# PWR_3V3.net
KiCad netlist of a schematic drawn in Altium Designer
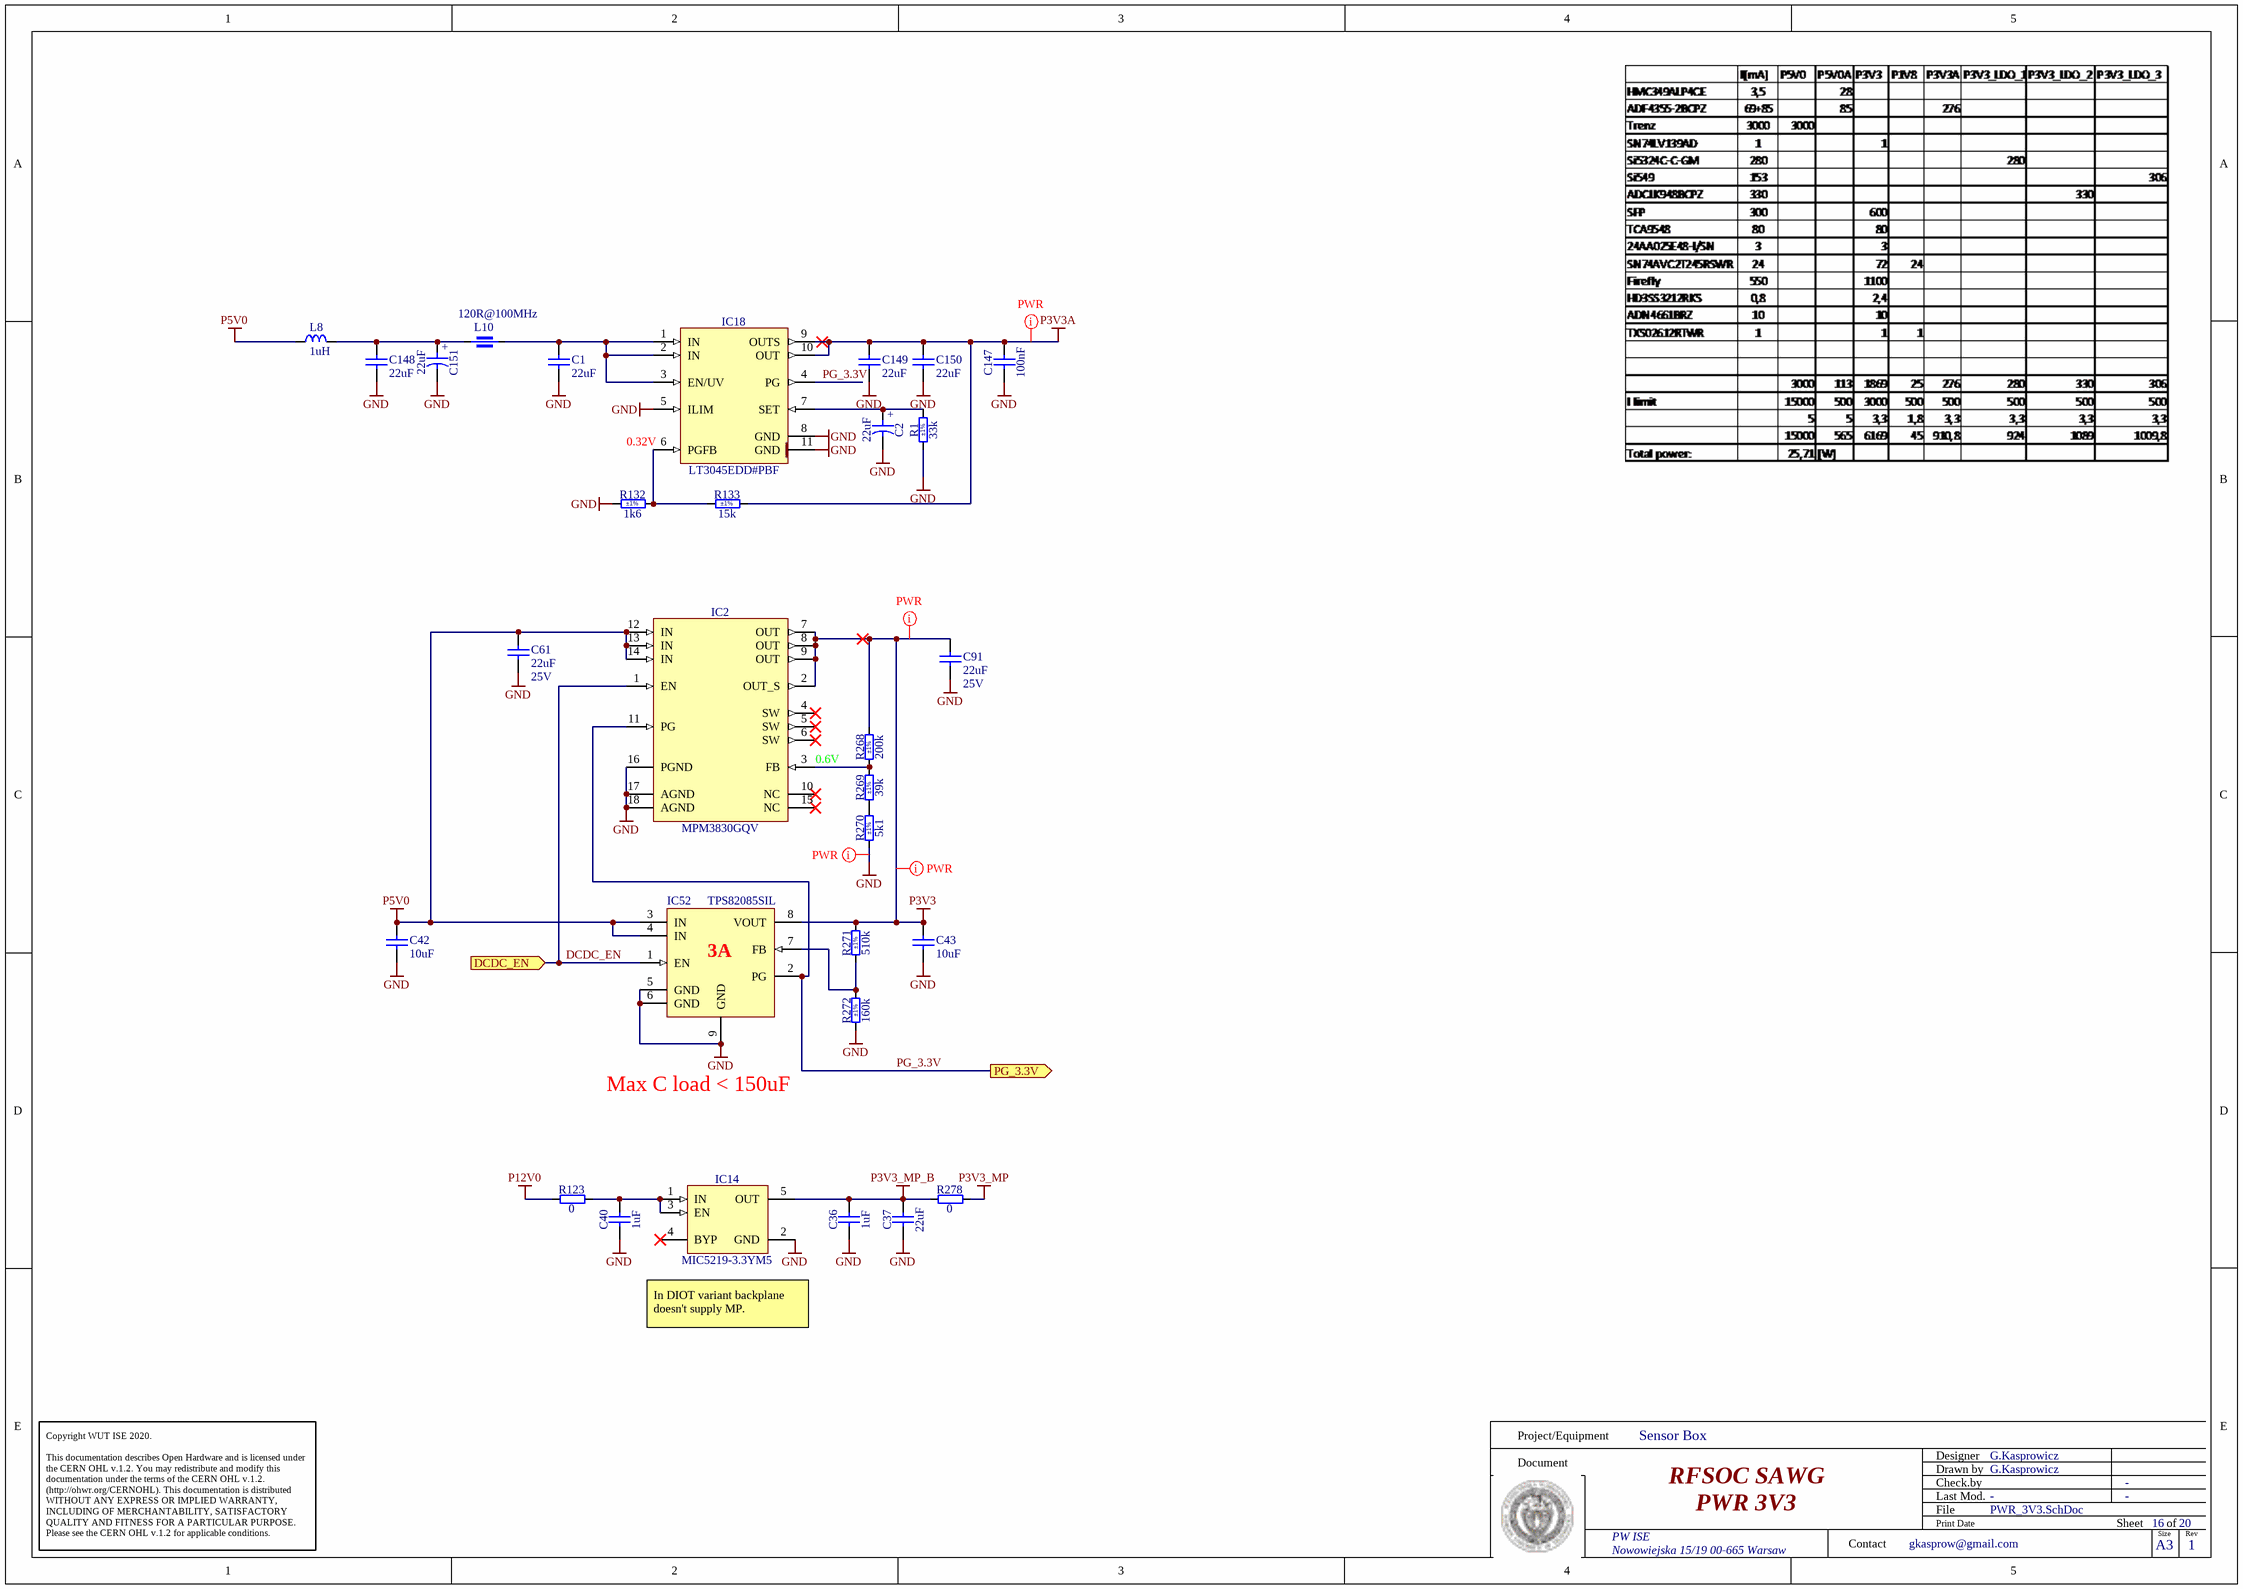
[diagram p0: PWR_3V3.SchDoc]

(export (version "E")
  (design (tool "Eeschema 10.0.6"))
  (components
    (comp (ref "C1")
      (value "22uF")
      (footprint "CAPC2012X135N")
      (description "Non-polarised capacitor")
      (fields
        (field (name "PART NUMBER") "CC0805_22UF_16V_10%_X5R")
        (field (name "VOLTAGE") "16V")
        (field (name "AUTHOR") "CERN DEM JLC")
      )
      (libsource (lib "Capacitors") (part "Capacitor - non polarized"))
    )
    (comp (ref "C2")
      (value "22uF")
      (footprint "CAPMP3528X210N")
      (description "Polarised capacitor")
      (fields
        (field (name "PART NUMBER") "CTE3528-21_22UF_10V_10%_LESR0700")
        (field (name "VOLTAGE") "10V")
        (field (name "AUTHOR") "CERN DEM JLC")
      )
      (libsource (lib "Capacitors") (part "Capacitor - polarized"))
    )
    (comp (ref "C36")
      (value "1uF")
      (footprint "CAPC1608X87N")
      (description "Non-polarised capacitor")
      (fields
        (field (name "PART NUMBER") "CC0603_1UF_25V_10%_X7R")
        (field (name "VOLTAGE") "25V")
        (field (name "AUTHOR") "CERN DEM JLC")
      )
      (libsource (lib "Capacitors") (part "Capacitor - non polarized"))
    )
    (comp (ref "C37")
      (value "22uF")
      (footprint "CAPC1608X90N")
      (description "Non-polarised capacitor")
      (fields
        (field (name "PART NUMBER") "CC0603_22UF_6.3V_20%_X5R")
        (field (name "VOLTAGE") "6.3V")
        (field (name "AUTHOR") "CERN DEM JLC")
      )
      (libsource (lib "Capacitors") (part "Capacitor - non polarized"))
    )
    (comp (ref "C40")
      (value "1uF")
      (footprint "CAPC1608X87N")
      (description "Non-polarised capacitor")
      (fields
        (field (name "PART NUMBER") "CC0603_1UF_25V_10%_X7R")
        (field (name "VOLTAGE") "25V")
        (field (name "AUTHOR") "CERN DEM JLC")
      )
      (libsource (lib "Capacitors") (part "Capacitor - non polarized"))
    )
    (comp (ref "C42")
      (value "10uF")
      (footprint "CAPC1608X80N")
      (description "Non-polarised capacitor")
      (fields
        (field (name "VOLTAGE") "16V")
        (field (name "TOLERANCE") "±20%")
        (field (name "AUTHOR") "CERN DEM MR")
      )
      (libsource (lib "Capacitors") (part "Capacitor - non polarized"))
    )
    (comp (ref "C43")
      (value "10uF")
      (footprint "CAPC1608X80N")
      (description "Non-polarised capacitor")
      (fields
        (field (name "VOLTAGE") "16V")
        (field (name "TOLERANCE") "±20%")
        (field (name "AUTHOR") "CERN DEM MR")
      )
      (libsource (lib "Capacitors") (part "Capacitor - non polarized"))
    )
    (comp (ref "C61")
      (value "22uF")
      (footprint "CAPC2012X145N")
      (description "Non-polarised capacitor")
      (fields
        (field (name "VOLTAGE") "25V")
        (field (name "TOLERANCE") "±20%")
        (field (name "PART NUMBER") "CC0805_22UF_25V_20%_X5R")
        (field (name "AUTHOR") "CERN DEM WB")
      )
      (libsource (lib "Capacitors") (part "Capacitor - non polarized"))
    )
    (comp (ref "C91")
      (value "22uF")
      (footprint "CAPC2012X145N")
      (description "Non-polarised capacitor")
      (fields
        (field (name "VOLTAGE") "25V")
        (field (name "TOLERANCE") "±20%")
        (field (name "PART NUMBER") "CC0805_22UF_25V_20%_X5R")
        (field (name "AUTHOR") "CERN DEM WB")
      )
      (libsource (lib "Capacitors") (part "Capacitor - non polarized"))
    )
    (comp (ref "C147")
      (value "100nF")
      (footprint "CAPC1005X55N")
      (description "Non-polarised capacitor")
      (fields
        (field (name "PART NUMBER") "CC0402_100NF_16V_10%_X5R")
        (field (name "VOLTAGE") "16V")
        (field (name "AUTHOR") "CERN DEM JLC")
      )
      (libsource (lib "Capacitors") (part "Capacitor - non polarized"))
    )
    (comp (ref "C148")
      (value "22uF")
      (footprint "CAPC2012X135N")
      (description "Non-polarised capacitor")
      (fields
        (field (name "PART NUMBER") "CC0805_22UF_16V_10%_X5R")
        (field (name "VOLTAGE") "16V")
        (field (name "AUTHOR") "CERN DEM JLC")
      )
      (libsource (lib "Capacitors") (part "Capacitor - non polarized"))
    )
    (comp (ref "C149")
      (value "22uF")
      (footprint "CAPC2012X135N")
      (description "Non-polarised capacitor")
      (fields
        (field (name "PART NUMBER") "CC0805_22UF_16V_10%_X5R")
        (field (name "VOLTAGE") "16V")
        (field (name "AUTHOR") "CERN DEM JLC")
      )
      (libsource (lib "Capacitors") (part "Capacitor - non polarized"))
    )
    (comp (ref "C150")
      (value "22uF")
      (footprint "CAPC2012X135N")
      (description "Non-polarised capacitor")
      (fields
        (field (name "PART NUMBER") "CC0805_22UF_16V_10%_X5R")
        (field (name "VOLTAGE") "16V")
        (field (name "AUTHOR") "CERN DEM JLC")
      )
      (libsource (lib "Capacitors") (part "Capacitor - non polarized"))
    )
    (comp (ref "C151")
      (value "22uF")
      (footprint "CAPMP3528X210N")
      (description "Polarised capacitor")
      (fields
        (field (name "PART NUMBER") "CTE3528-21_22UF_10V_10%_LESR0700")
        (field (name "VOLTAGE") "10V")
        (field (name "AUTHOR") "CERN DEM JLC")
      )
      (libsource (lib "Capacitors") (part "Capacitor - polarized"))
    )
    (comp (ref "IC2")
      (value "MPM3830GQV")
      (footprint "MPS_MPM38XXGQV")
      (description "2.8V to 5.5V Input, 4A, Power Module Synchronous Step-Down Converter with Integrated Inductor")
      (fields
        (field (name "MANUFACTURER") "MPS (MONOLITIC  POWER SYSTEMS)")
        (field (name "AUTHOR") "CERN DEM BC")
      )
      (libsource (lib "ICs And Semiconductors") (part "MPM3830GQV"))
    )
    (comp (ref "IC14")
      (value "MIC5219-3.3YM5")
      (footprint "SOT95P280X145-5N")
      (description "500mA Peak Output LDO Regulator")
      (fields (field (name "MANUFACTURER") "MICROCHIP TECHNOLOGY") (field (name "AUTHOR") "CERN DEM WB"))
      (libsource (lib "ICs And Semiconductors") (part "MIC5219-X.XYM5"))
    )
    (comp (ref "IC18")
      (value "LT3045EDD#PBF")
      (footprint "SON50P300X300X80-11N-R175X248")
      (description "20V, 500mA, Ultralow Noise, Ultrahigh PSRR Linear Regulator")
      (fields (field (name "MANUFACTURER") "LINEAR TECHNOLOGY") (field (name "AUTHOR") "CERN DEM JLC"))
      (libsource (lib "ICs And Semiconductors") (part "LT3045EDD"))
    )
    (comp (ref "IC52")
      (value "TPS82085SIL")
      (footprint "TPS82085SILR")
      (libsource (lib "TE") (part "TPS82085"))
    )
    (comp (ref "L8")
      (value "1uH")
      (footprint "INDC2520X120N")
      (description "Inductor")
      (fields
        (field (name "TOLERANCE") "±20%")
        (field (name "PART NUMBER") "IND1008_1UH_20%_TDK_TFM252012ALVA1R0M")
        (field (name "AUTHOR") "CERN DEM BC")
      )
      (libsource (lib "Inductors & Transformers") (part "Inductor"))
    )
    (comp (ref "L10")
      (value "120R@100MHz")
      (footprint "INDC1608X65N")
      (fields
        (field (name "PART NUMBER") "IND0603_MURATA_BLM18SG121TN1D")
        (field (name "POWER") "3A")
        (field (name "TOLERANCE") "±25%")
        (field (name "AUTHOR") "CERN DEM JLC")
      )
      (libsource (lib "Inductors & Transformers") (part "Ferrite Bead"))
    )
    (comp (ref "R1")
      (value "33k")
      (footprint "RESC1005X40N")
      (description "Resistor - 1%")
      (fields
        (field (name "TOLERANCE") "±1%")
        (field (name "PART NUMBER") "R0402_33K_1%_0.0625W_100PPM")
        (field (name "POWER") "0.0625W")
        (field (name "AUTHOR") "CERN DEM JLC")
      )
      (libsource (lib "Resistors") (part "Resistor - 1%"))
    )
    (comp (ref "R123")
      (value "0")
      (footprint "RESC1005X40N")
      (description "Resistor")
      (fields
        (field (name "PART NUMBER") "R0402_0R_JUMPER")
        (field (name "MANUFACTURER") "GENERIC")
        (field (name "AUTHOR") "CERN DEM JLC")
      )
      (libsource (lib "Resistors") (part "Resistor"))
    )
    (comp (ref "R132")
      (value "1k6")
      (footprint "RESC1005X40N")
      (description "Resistor - 1%")
      (fields
        (field (name "TOLERANCE") "±1%")
        (field (name "PART NUMBER") "R0402_1K6_1%_0.0625W_100PPM")
        (field (name "POWER") "0.0625W")
        (field (name "AUTHOR") "CERN DEM JLC")
      )
      (libsource (lib "Resistors") (part "Resistor - 1%"))
    )
    (comp (ref "R133")
      (value "15k")
      (footprint "RESC1005X40N")
      (description "Resistor - 1%")
      (fields
        (field (name "TOLERANCE") "±1%")
        (field (name "PART NUMBER") "R0402_15K_1%_0.0625W_100PPM")
        (field (name "POWER") "0.0625W")
        (field (name "AUTHOR") "CERN DEM JMW")
      )
      (libsource (lib "Resistors") (part "Resistor - 1%"))
    )
    (comp (ref "R268")
      (value "200k")
      (footprint "RESC1005X40N")
      (description "Resistor - 1%")
      (fields
        (field (name "TOLERANCE") "±1%")
        (field (name "PART NUMBER") "R0402_200K_1%_0.0625W_100PPM")
        (field (name "POWER") "0.0625W")
        (field (name "AUTHOR") "CERN DEM JLC")
      )
      (libsource (lib "Resistors") (part "Resistor - 1%"))
    )
    (comp (ref "R269")
      (value "39k")
      (footprint "RESC1005X40N")
      (description "Resistor - 1%")
      (fields
        (field (name "TOLERANCE") "±1%")
        (field (name "PART NUMBER") "R0402_39K_1%_0.0625W_100PPM")
        (field (name "POWER") "0.0625W")
        (field (name "AUTHOR") "CERN DEM JLC")
      )
      (libsource (lib "Resistors") (part "Resistor - 1%"))
    )
    (comp (ref "R270")
      (value "5k1")
      (footprint "RESC1005X40N")
      (description "Resistor - 1%")
      (fields
        (field (name "TOLERANCE") "±1%")
        (field (name "PART NUMBER") "R0402_5K1_1%_0.0625W_100PPM")
        (field (name "POWER") "0.0625W")
        (field (name "AUTHOR") "CERN DEM JLC")
      )
      (libsource (lib "Resistors") (part "Resistor - 1%"))
    )
    (comp (ref "R271")
      (value "510k")
      (footprint "RESC1005X40N")
      (description "Resistor - 1%")
      (fields
        (field (name "TOLERANCE") "±1%")
        (field (name "PART NUMBER") "R0402_510K_1%_0.0625W_100PPM")
        (field (name "POWER") "0.0625W")
        (field (name "AUTHOR") "CERN DEM JLC")
      )
      (libsource (lib "Resistors") (part "Resistor - 1%"))
    )
    (comp (ref "R272")
      (value "160k")
      (footprint "RESC1005X40N")
      (description "Resistor - 1%")
      (fields
        (field (name "TOLERANCE") "±1%")
        (field (name "PART NUMBER") "R0402_160K_1%_0.0625W_100PPM")
        (field (name "POWER") "0.0625W")
        (field (name "AUTHOR") "CERN DEM JLC")
      )
      (libsource (lib "Resistors") (part "Resistor - 1%"))
    )
    (comp (ref "R278")
      (value "0")
      (footprint "RESC1005X40N")
      (description "Resistor")
      (fields
        (field (name "PART NUMBER") "R0402_0R_JUMPER")
        (field (name "MANUFACTURER") "GENERIC")
        (field (name "AUTHOR") "CERN DEM JLC")
      )
      (libsource (lib "Resistors") (part "Resistor"))
    )
  )
  (nets
    (net (code "1") (name "/DCDC_EN") (class "Default")
      (node (ref "IC2") (pin "1") (pinfunction "EN_1") (pintype "input"))
      (node (ref "IC52") (pin "1") (pinfunction "EN_1") (pintype "input"))
    )
    (net (code "2") (name "/PG_3.3V") (class "Default")
      (node (ref "IC18") (pin "4") (pinfunction "PG_4") (pintype "output"))
      (node (ref "IC2") (pin "11") (pinfunction "PG_11") (pintype "input"))
      (node (ref "IC52") (pin "2") (pinfunction "PG_2") (pintype "open_collector"))
    )
    (net (code "3") (name "GND") (class "Default")
      (node (ref "C1") (pin "2") (pinfunction "2_2") (pintype "passive"))
      (node (ref "C147") (pin "1") (pinfunction "1_1") (pintype "passive"))
      (node (ref "C148") (pin "2") (pinfunction "2_2") (pintype "passive"))
      (node (ref "C149") (pin "2") (pinfunction "2_2") (pintype "passive"))
      (node (ref "C150") (pin "2") (pinfunction "2_2") (pintype "passive"))
      (node (ref "C151") (pin "2") (pinfunction "2_2") (pintype "passive"))
      (node (ref "C2") (pin "2") (pinfunction "2_2") (pintype "passive"))
      (node (ref "C36") (pin "1") (pinfunction "1_1") (pintype "passive"))
      (node (ref "C37") (pin "1") (pinfunction "1_1") (pintype "passive"))
      (node (ref "C40") (pin "1") (pinfunction "1_1") (pintype "passive"))
      (node (ref "C42") (pin "2") (pinfunction "2_2") (pintype "passive"))
      (node (ref "C43") (pin "2") (pinfunction "2_2") (pintype "passive"))
      (node (ref "C61") (pin "1") (pinfunction "1_1") (pintype "passive"))
      (node (ref "C91") (pin "1") (pinfunction "1_1") (pintype "passive"))
      (node (ref "IC14") (pin "2") (pinfunction "GND_2") (pintype "power_in"))
      (node (ref "IC18") (pin "11") (pinfunction "GND_11") (pintype "power_in"))
      (node (ref "IC18") (pin "5") (pinfunction "ILIM_5") (pintype "input"))
      (node (ref "IC18") (pin "8") (pinfunction "GND_8") (pintype "power_in"))
      (node (ref "IC2") (pin "16") (pinfunction "PGND_16") (pintype "power_in"))
      (node (ref "IC2") (pin "17") (pinfunction "AGND_17") (pintype "power_in"))
      (node (ref "IC2") (pin "18") (pinfunction "AGND_18") (pintype "power_in"))
      (node (ref "IC52") (pin "5") (pinfunction "GND_5") (pintype "power_in"))
      (node (ref "IC52") (pin "6") (pinfunction "GND_6") (pintype "power_in"))
      (node (ref "IC52") (pin "9") (pinfunction "GND_9") (pintype "power_in"))
      (node (ref "R1") (pin "1") (pinfunction "1_1") (pintype "passive"))
      (node (ref "R132") (pin "1") (pinfunction "1_1") (pintype "passive"))
      (node (ref "R270") (pin "1") (pinfunction "1_1") (pintype "passive"))
      (node (ref "R272") (pin "1") (pinfunction "1_1") (pintype "passive"))
    )
    (net (code "4") (name "Net-(C148-Pad1)") (class "Default")
      (node (ref "C148") (pin "1") (pinfunction "1_1") (pintype "passive"))
      (node (ref "C151") (pin "1") (pinfunction "1_1") (pintype "passive"))
      (node (ref "L10") (pin "1") (pinfunction "1_1") (pintype "passive"))
      (node (ref "L8") (pin "2") (pinfunction "2_2") (pintype "passive"))
    )
    (net (code "5") (name "Net-(IC2-FB)") (class "Default")
      (node (ref "IC2") (pin "3") (pinfunction "FB_3") (pintype "input"))
      (node (ref "R268") (pin "1") (pinfunction "1_1") (pintype "passive"))
      (node (ref "R269") (pin "2") (pinfunction "2_2") (pintype "passive"))
    )
    (net (code "6") (name "Net-(IC14-EN)") (class "Default")
      (node (ref "C40") (pin "2") (pinfunction "2_2") (pintype "passive"))
      (node (ref "IC14") (pin "1") (pinfunction "IN_1") (pintype "input"))
      (node (ref "IC14") (pin "3") (pinfunction "EN_3") (pintype "input"))
      (node (ref "R123") (pin "2") (pinfunction "2_2") (pintype "passive"))
    )
    (net (code "7") (name "Net-(IC18-EN{slash}UV)") (class "Default")
      (node (ref "C1") (pin "1") (pinfunction "1_1") (pintype "passive"))
      (node (ref "IC18") (pin "1") (pinfunction "IN_1") (pintype "input"))
      (node (ref "IC18") (pin "2") (pinfunction "IN_2") (pintype "input"))
      (node (ref "IC18") (pin "3") (pinfunction "EN/UV_3") (pintype "input"))
      (node (ref "L10") (pin "2") (pinfunction "2_2") (pintype "passive"))
    )
    (net (code "8") (name "Net-(IC18-PGFB)") (class "Default")
      (node (ref "IC18") (pin "6") (pinfunction "PGFB_6") (pintype "input"))
      (node (ref "R132") (pin "2") (pinfunction "2_2") (pintype "passive"))
      (node (ref "R133") (pin "1") (pinfunction "1_1") (pintype "passive"))
    )
    (net (code "9") (name "Net-(IC18-SET)") (class "Default")
      (node (ref "C2") (pin "1") (pinfunction "1_1") (pintype "passive"))
      (node (ref "IC18") (pin "7") (pinfunction "SET_7") (pintype "input"))
      (node (ref "R1") (pin "2") (pinfunction "2_2") (pintype "passive"))
    )
    (net (code "10") (name "Net-(IC52-FB)") (class "Default")
      (node (ref "IC52") (pin "7") (pinfunction "FB_7") (pintype "input"))
      (node (ref "R271") (pin "1") (pinfunction "1_1") (pintype "passive"))
      (node (ref "R272") (pin "2") (pinfunction "2_2") (pintype "passive"))
    )
    (net (code "11") (name "Net-(R269-Pad1)") (class "Default")
      (node (ref "R269") (pin "1") (pinfunction "1_1") (pintype "passive"))
      (node (ref "R270") (pin "2") (pinfunction "2_2") (pintype "passive"))
    )
    (net (code "12") (name "P3V3") (class "Default")
      (node (ref "C43") (pin "1") (pinfunction "1_1") (pintype "passive"))
      (node (ref "C91") (pin "2") (pinfunction "2_2") (pintype "passive"))
      (node (ref "IC2") (pin "2") (pinfunction "OUT_S_2") (pintype "output"))
      (node (ref "IC2") (pin "7") (pinfunction "OUT_7") (pintype "output"))
      (node (ref "IC2") (pin "8") (pinfunction "OUT_8") (pintype "output"))
      (node (ref "IC2") (pin "9") (pinfunction "OUT_9") (pintype "output"))
      (node (ref "IC52") (pin "8") (pinfunction "VOUT_8") (pintype "power_in"))
      (node (ref "R268") (pin "2") (pinfunction "2_2") (pintype "passive"))
      (node (ref "R271") (pin "2") (pinfunction "2_2") (pintype "passive"))
    )
    (net (code "13") (name "P3V3A") (class "Default")
      (node (ref "C147") (pin "2") (pinfunction "2_2") (pintype "passive"))
      (node (ref "C149") (pin "1") (pinfunction "1_1") (pintype "passive"))
      (node (ref "C150") (pin "1") (pinfunction "1_1") (pintype "passive"))
      (node (ref "IC18") (pin "10") (pinfunction "OUT_10") (pintype "output"))
      (node (ref "IC18") (pin "9") (pinfunction "OUTS_9") (pintype "output"))
      (node (ref "R133") (pin "2") (pinfunction "2_2") (pintype "passive"))
    )
    (net (code "14") (name "P3V3_MP") (class "Default")
      (node (ref "R278") (pin "2") (pinfunction "2_2") (pintype "passive"))
    )
    (net (code "15") (name "P3V3_MP_B") (class "Default")
      (node (ref "C36") (pin "2") (pinfunction "2_2") (pintype "passive"))
      (node (ref "C37") (pin "2") (pinfunction "2_2") (pintype "passive"))
      (node (ref "IC14") (pin "5") (pinfunction "OUT_5") (pintype "power_in"))
      (node (ref "R278") (pin "1") (pinfunction "1_1") (pintype "passive"))
    )
    (net (code "16") (name "P5V0") (class "Default")
      (node (ref "C42") (pin "1") (pinfunction "1_1") (pintype "passive"))
      (node (ref "C61") (pin "2") (pinfunction "2_2") (pintype "passive"))
      (node (ref "IC2") (pin "12") (pinfunction "IN_12") (pintype "input"))
      (node (ref "IC2") (pin "13") (pinfunction "IN_13") (pintype "input"))
      (node (ref "IC2") (pin "14") (pinfunction "IN_14") (pintype "input"))
      (node (ref "IC52") (pin "3") (pinfunction "IN_3") (pintype "power_in"))
      (node (ref "IC52") (pin "4") (pinfunction "IN_4") (pintype "power_in"))
      (node (ref "L8") (pin "1") (pinfunction "1_1") (pintype "passive"))
    )
    (net (code "17") (name "P12V0") (class "Default")
      (node (ref "R123") (pin "1") (pinfunction "1_1") (pintype "passive"))
    )
    (net (code "18") (name "unconnected-(IC2-NC-Pad10)") (class "Default")
      (node (ref "IC2") (pin "10") (pinfunction "NC_10") (pintype "passive+no_connect"))
    )
    (net (code "19") (name "unconnected-(IC2-NC-Pad15)") (class "Default")
      (node (ref "IC2") (pin "15") (pinfunction "NC_15") (pintype "passive+no_connect"))
    )
    (net (code "20") (name "unconnected-(IC2-SW-Pad4)") (class "Default")
      (node (ref "IC2") (pin "4") (pinfunction "SW_4") (pintype "output+no_connect"))
    )
    (net (code "21") (name "unconnected-(IC2-SW-Pad5)") (class "Default")
      (node (ref "IC2") (pin "5") (pinfunction "SW_5") (pintype "output+no_connect"))
    )
    (net (code "22") (name "unconnected-(IC2-SW-Pad6)") (class "Default")
      (node (ref "IC2") (pin "6") (pinfunction "SW_6") (pintype "output+no_connect"))
    )
    (net (code "23") (name "unconnected-(IC14-BYP-Pad4)") (class "Default")
      (node (ref "IC14") (pin "4") (pinfunction "BYP_4") (pintype "passive+no_connect"))
    )
  )
)
